# rpi_vga.net
KiCad netlist of a schematic drawn in EAGLE
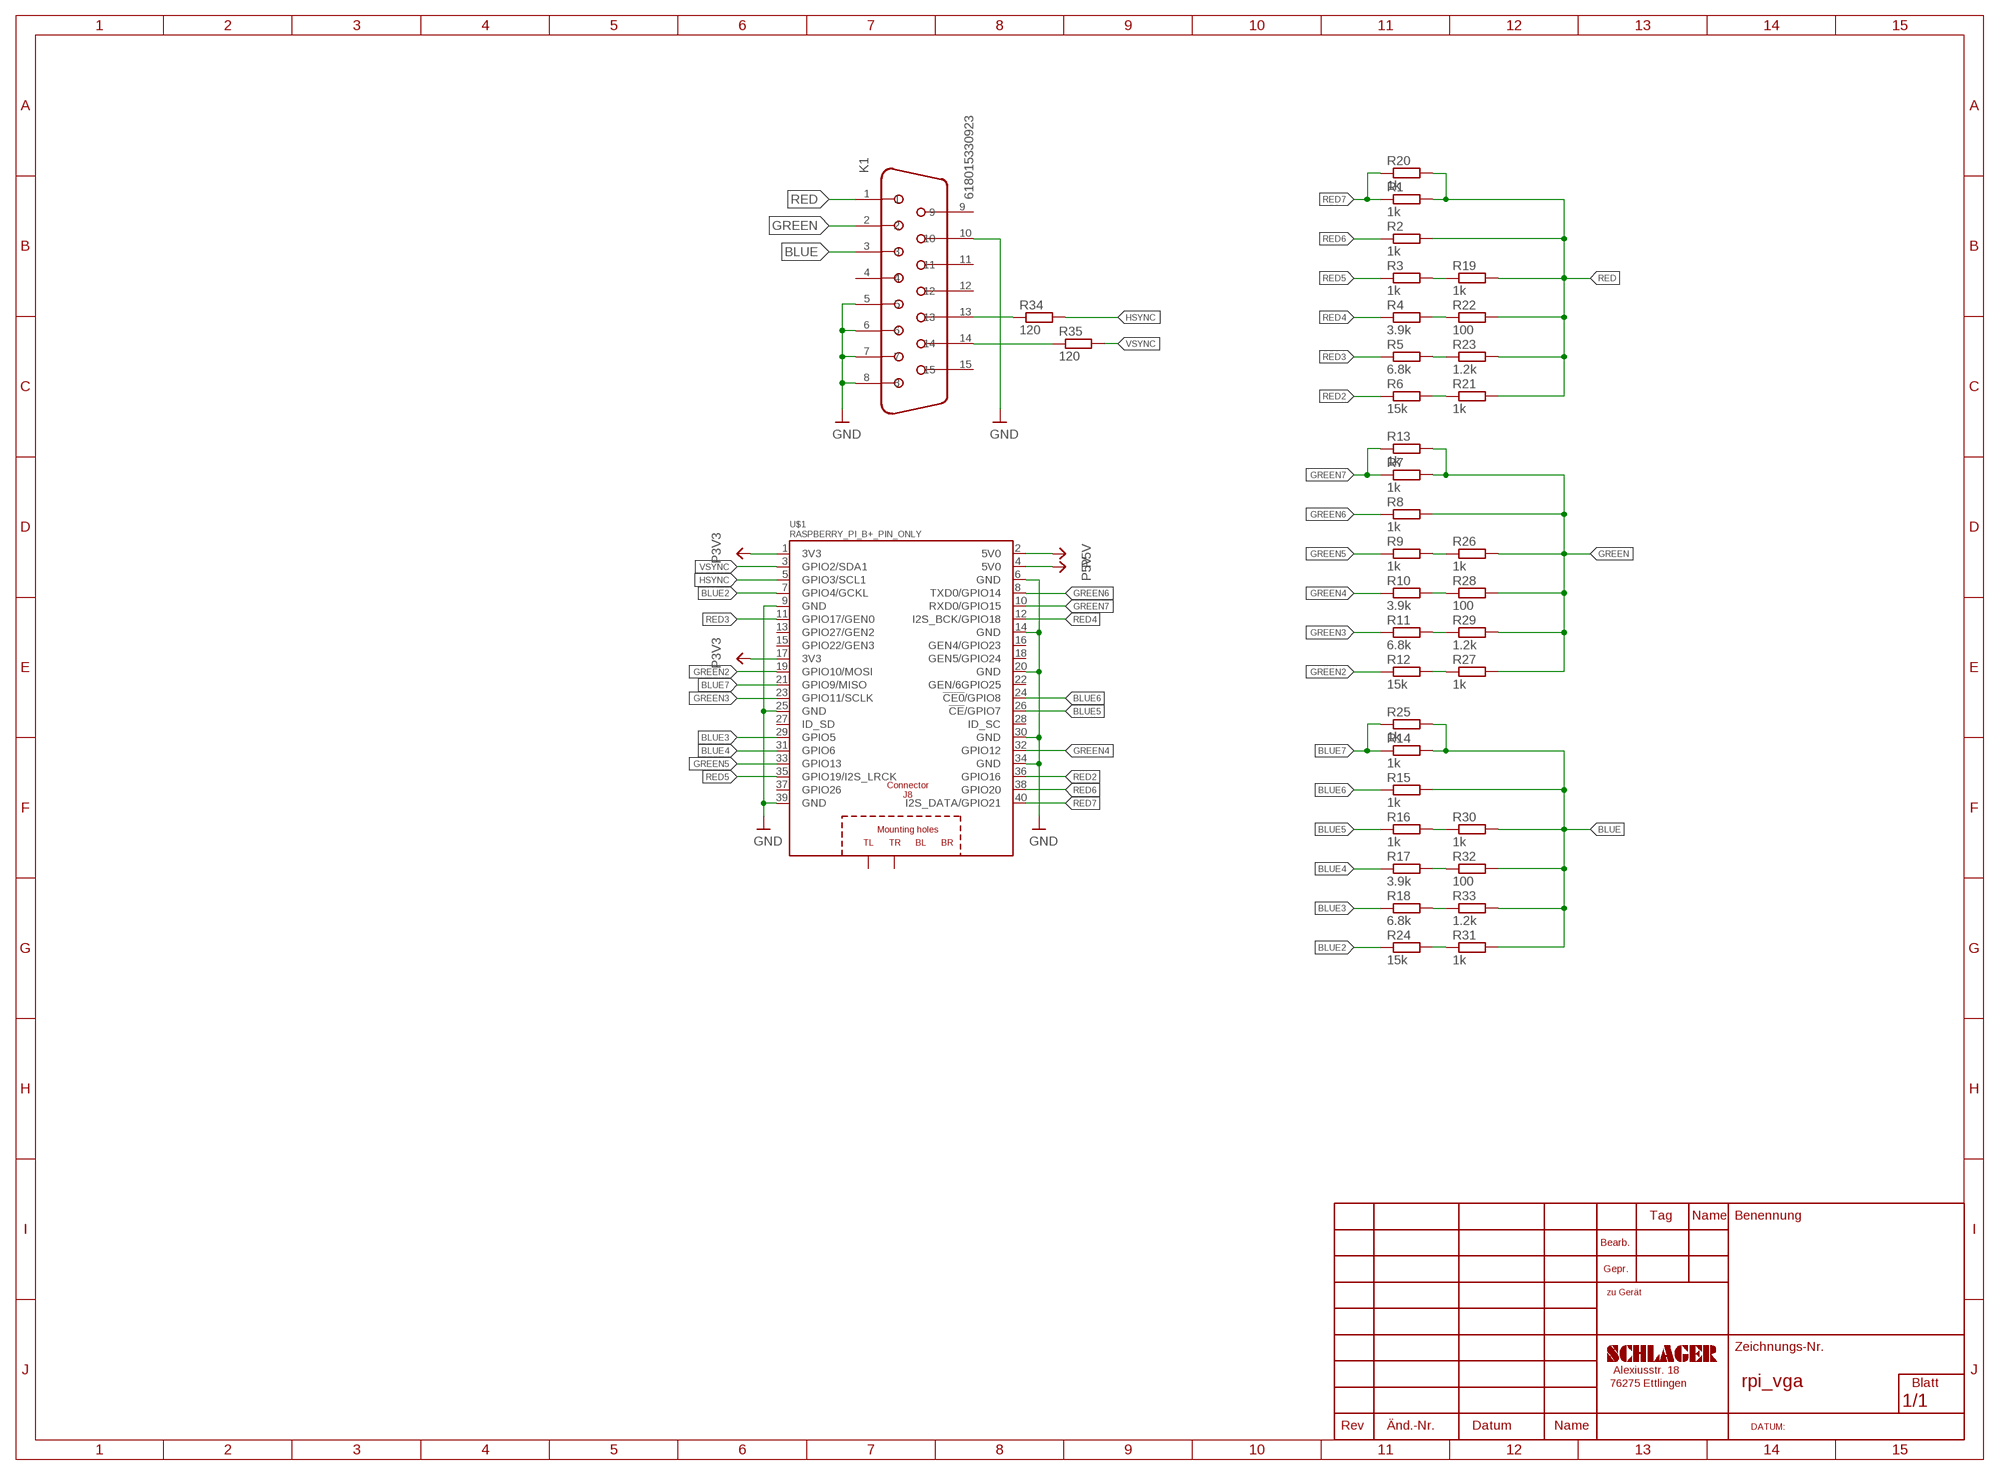
[diagram p0: schematic, sheet 1]

(export (version "E")
  (design (tool "Eeschema 10.0.6"))
  (components
    (comp (ref "K1")
      (value "618015330923")
      (footprint "eagle-import:618015330923")
      (libsource (lib "eagle-import") (part "618015330923"))
    )
    (comp (ref "R1")
      (value "1k")
      (footprint "eagle-import:R0603")
      (libsource (lib "eagle-import") (part "R-EU_R0603"))
    )
    (comp (ref "R2")
      (value "1k")
      (footprint "eagle-import:R0603")
      (libsource (lib "eagle-import") (part "R-EU_R0603"))
    )
    (comp (ref "R3")
      (value "1k")
      (footprint "eagle-import:R0603")
      (libsource (lib "eagle-import") (part "R-EU_R0603"))
    )
    (comp (ref "R4")
      (value "3.9k")
      (footprint "eagle-import:R0603")
      (libsource (lib "eagle-import") (part "R-EU_R0603"))
    )
    (comp (ref "R5")
      (value "6.8k")
      (footprint "eagle-import:R0603")
      (libsource (lib "eagle-import") (part "R-EU_R0603"))
    )
    (comp (ref "R6")
      (value "15k")
      (footprint "eagle-import:R0603")
      (libsource (lib "eagle-import") (part "R-EU_R0603"))
    )
    (comp (ref "R7")
      (value "1k")
      (footprint "eagle-import:R0603")
      (libsource (lib "eagle-import") (part "R-EU_R0603"))
    )
    (comp (ref "R8")
      (value "1k")
      (footprint "eagle-import:R0603")
      (libsource (lib "eagle-import") (part "R-EU_R0603"))
    )
    (comp (ref "R9")
      (value "1k")
      (footprint "eagle-import:R0603")
      (libsource (lib "eagle-import") (part "R-EU_R0603"))
    )
    (comp (ref "R10")
      (value "3.9k")
      (footprint "eagle-import:R0603")
      (libsource (lib "eagle-import") (part "R-EU_R0603"))
    )
    (comp (ref "R11")
      (value "6.8k")
      (footprint "eagle-import:R0603")
      (libsource (lib "eagle-import") (part "R-EU_R0603"))
    )
    (comp (ref "R12")
      (value "15k")
      (footprint "eagle-import:R0603")
      (libsource (lib "eagle-import") (part "R-EU_R0603"))
    )
    (comp (ref "R13")
      (value "1k")
      (footprint "eagle-import:R0603")
      (libsource (lib "eagle-import") (part "R-EU_R0603"))
    )
    (comp (ref "R14")
      (value "1k")
      (footprint "eagle-import:R0603")
      (libsource (lib "eagle-import") (part "R-EU_R0603"))
    )
    (comp (ref "R15")
      (value "1k")
      (footprint "eagle-import:R0603")
      (libsource (lib "eagle-import") (part "R-EU_R0603"))
    )
    (comp (ref "R16")
      (value "1k")
      (footprint "eagle-import:R0603")
      (libsource (lib "eagle-import") (part "R-EU_R0603"))
    )
    (comp (ref "R17")
      (value "3.9k")
      (footprint "eagle-import:R0603")
      (libsource (lib "eagle-import") (part "R-EU_R0603"))
    )
    (comp (ref "R18")
      (value "6.8k")
      (footprint "eagle-import:R0603")
      (libsource (lib "eagle-import") (part "R-EU_R0603"))
    )
    (comp (ref "R19")
      (value "1k")
      (footprint "eagle-import:R0603")
      (libsource (lib "eagle-import") (part "R-EU_R0603"))
    )
    (comp (ref "R20")
      (value "1k")
      (footprint "eagle-import:R0603")
      (libsource (lib "eagle-import") (part "R-EU_R0603"))
    )
    (comp (ref "R21")
      (value "1k")
      (footprint "eagle-import:R0603")
      (libsource (lib "eagle-import") (part "R-EU_R0603"))
    )
    (comp (ref "R22")
      (value "100")
      (footprint "eagle-import:R0603")
      (libsource (lib "eagle-import") (part "R-EU_R0603"))
    )
    (comp (ref "R23")
      (value "1.2k")
      (footprint "eagle-import:R0603")
      (libsource (lib "eagle-import") (part "R-EU_R0603"))
    )
    (comp (ref "R24")
      (value "15k")
      (footprint "eagle-import:R0603")
      (libsource (lib "eagle-import") (part "R-EU_R0603"))
    )
    (comp (ref "R25")
      (value "1k")
      (footprint "eagle-import:R0603")
      (libsource (lib "eagle-import") (part "R-EU_R0603"))
    )
    (comp (ref "R26")
      (value "1k")
      (footprint "eagle-import:R0603")
      (libsource (lib "eagle-import") (part "R-EU_R0603"))
    )
    (comp (ref "R27")
      (value "1k")
      (footprint "eagle-import:R0603")
      (libsource (lib "eagle-import") (part "R-EU_R0603"))
    )
    (comp (ref "R28")
      (value "100")
      (footprint "eagle-import:R0603")
      (libsource (lib "eagle-import") (part "R-EU_R0603"))
    )
    (comp (ref "R29")
      (value "1.2k")
      (footprint "eagle-import:R0603")
      (libsource (lib "eagle-import") (part "R-EU_R0603"))
    )
    (comp (ref "R30")
      (value "1k")
      (footprint "eagle-import:R0603")
      (libsource (lib "eagle-import") (part "R-EU_R0603"))
    )
    (comp (ref "R31")
      (value "1k")
      (footprint "eagle-import:R0603")
      (libsource (lib "eagle-import") (part "R-EU_R0603"))
    )
    (comp (ref "R32")
      (value "100")
      (footprint "eagle-import:R0603")
      (libsource (lib "eagle-import") (part "R-EU_R0603"))
    )
    (comp (ref "R33")
      (value "1.2k")
      (footprint "eagle-import:R0603")
      (libsource (lib "eagle-import") (part "R-EU_R0603"))
    )
    (comp (ref "R34")
      (value "120")
      (footprint "eagle-import:R0603")
      (libsource (lib "eagle-import") (part "R-EU_R0603"))
    )
    (comp (ref "R35")
      (value "120")
      (footprint "eagle-import:R0603")
      (libsource (lib "eagle-import") (part "R-EU_R0603"))
    )
    (comp (ref "U$1")
      (value "RASPBERRY_PI_B+_PIN_ONLY")
      (footprint "eagle-import:RASPBERRY_PI_B+_PIN_ONLY")
      (libsource (lib "eagle-import") (part "RASPBERRY_PI_B+_PIN_ONLY"))
    )
  )
  (nets
    (net (code "1") (name "BLUE") (class "Default")
      (node (ref "K1") (pin "3") (pinfunction "3_3") (pintype "bidirectional"))
      (node (ref "R14") (pin "2") (pinfunction "2_2") (pintype "passive"))
      (node (ref "R15") (pin "2") (pinfunction "2_2") (pintype "passive"))
      (node (ref "R25") (pin "2") (pinfunction "2_2") (pintype "passive"))
      (node (ref "R30") (pin "2") (pinfunction "2_2") (pintype "passive"))
      (node (ref "R31") (pin "2") (pinfunction "2_2") (pintype "passive"))
      (node (ref "R32") (pin "2") (pinfunction "2_2") (pintype "passive"))
      (node (ref "R33") (pin "2") (pinfunction "2_2") (pintype "passive"))
    )
    (net (code "2") (name "BLUE2") (class "Default")
      (node (ref "R24") (pin "1") (pinfunction "1_1") (pintype "passive"))
      (node (ref "U$1") (pin "7") (pinfunction "GPIO4/GCKL_7") (pintype "bidirectional"))
    )
    (net (code "3") (name "BLUE3") (class "Default")
      (node (ref "R18") (pin "1") (pinfunction "1_1") (pintype "passive"))
      (node (ref "U$1") (pin "29") (pinfunction "GPIO5_29") (pintype "bidirectional"))
    )
    (net (code "4") (name "BLUE4") (class "Default")
      (node (ref "R17") (pin "1") (pinfunction "1_1") (pintype "passive"))
      (node (ref "U$1") (pin "31") (pinfunction "GPIO6_31") (pintype "bidirectional"))
    )
    (net (code "5") (name "BLUE5") (class "Default")
      (node (ref "R16") (pin "1") (pinfunction "1_1") (pintype "passive"))
      (node (ref "U$1") (pin "26") (pinfunction "~{CE}/GPIO7_26") (pintype "bidirectional"))
    )
    (net (code "6") (name "BLUE6") (class "Default")
      (node (ref "R15") (pin "1") (pinfunction "1_1") (pintype "passive"))
      (node (ref "U$1") (pin "24") (pinfunction "~{CE0}/GPIO8_24") (pintype "bidirectional"))
    )
    (net (code "7") (name "BLUE7") (class "Default")
      (node (ref "R14") (pin "1") (pinfunction "1_1") (pintype "passive"))
      (node (ref "R25") (pin "1") (pinfunction "1_1") (pintype "passive"))
      (node (ref "U$1") (pin "21") (pinfunction "GPIO9/MISO_21") (pintype "bidirectional"))
    )
    (net (code "8") (name "GND") (class "Default")
      (node (ref "K1") (pin "10") (pinfunction "10_10") (pintype "bidirectional"))
      (node (ref "K1") (pin "5") (pinfunction "5_5") (pintype "bidirectional"))
      (node (ref "K1") (pin "6") (pinfunction "6_6") (pintype "bidirectional"))
      (node (ref "K1") (pin "7") (pinfunction "7_7") (pintype "bidirectional"))
      (node (ref "K1") (pin "8") (pinfunction "8_8") (pintype "bidirectional"))
      (node (ref "U$1") (pin "14") (pinfunction "GND_14") (pintype "power_in"))
      (node (ref "U$1") (pin "20") (pinfunction "GND_20") (pintype "power_in"))
      (node (ref "U$1") (pin "25") (pinfunction "GND_25") (pintype "power_in"))
      (node (ref "U$1") (pin "30") (pinfunction "GND_30") (pintype "power_in"))
      (node (ref "U$1") (pin "34") (pinfunction "GND_34") (pintype "power_in"))
      (node (ref "U$1") (pin "39") (pinfunction "GND_39") (pintype "power_in"))
      (node (ref "U$1") (pin "6") (pinfunction "GND_6") (pintype "power_in"))
      (node (ref "U$1") (pin "9") (pinfunction "GND_9") (pintype "power_in"))
    )
    (net (code "9") (name "GREEN") (class "Default")
      (node (ref "K1") (pin "2") (pinfunction "2_2") (pintype "bidirectional"))
      (node (ref "R13") (pin "2") (pinfunction "2_2") (pintype "passive"))
      (node (ref "R26") (pin "2") (pinfunction "2_2") (pintype "passive"))
      (node (ref "R27") (pin "2") (pinfunction "2_2") (pintype "passive"))
      (node (ref "R28") (pin "2") (pinfunction "2_2") (pintype "passive"))
      (node (ref "R29") (pin "2") (pinfunction "2_2") (pintype "passive"))
      (node (ref "R7") (pin "2") (pinfunction "2_2") (pintype "passive"))
      (node (ref "R8") (pin "2") (pinfunction "2_2") (pintype "passive"))
    )
    (net (code "10") (name "GREEN2") (class "Default")
      (node (ref "R12") (pin "1") (pinfunction "1_1") (pintype "passive"))
      (node (ref "U$1") (pin "19") (pinfunction "GPIO10/MOSI_19") (pintype "bidirectional"))
    )
    (net (code "11") (name "GREEN3") (class "Default")
      (node (ref "R11") (pin "1") (pinfunction "1_1") (pintype "passive"))
      (node (ref "U$1") (pin "23") (pinfunction "GPIO11/SCLK_23") (pintype "bidirectional"))
    )
    (net (code "12") (name "GREEN4") (class "Default")
      (node (ref "R10") (pin "1") (pinfunction "1_1") (pintype "passive"))
      (node (ref "U$1") (pin "32") (pinfunction "GPIO12_32") (pintype "bidirectional"))
    )
    (net (code "13") (name "GREEN5") (class "Default")
      (node (ref "R9") (pin "1") (pinfunction "1_1") (pintype "passive"))
      (node (ref "U$1") (pin "33") (pinfunction "GPIO13_33") (pintype "bidirectional"))
    )
    (net (code "14") (name "GREEN6") (class "Default")
      (node (ref "R8") (pin "1") (pinfunction "1_1") (pintype "passive"))
      (node (ref "U$1") (pin "8") (pinfunction "TXD0/GPIO14_8") (pintype "bidirectional"))
    )
    (net (code "15") (name "GREEN7") (class "Default")
      (node (ref "R13") (pin "1") (pinfunction "1_1") (pintype "passive"))
      (node (ref "R7") (pin "1") (pinfunction "1_1") (pintype "passive"))
      (node (ref "U$1") (pin "10") (pinfunction "RXD0/GPIO15_10") (pintype "bidirectional"))
    )
    (net (code "16") (name "HSYNC") (class "Default")
      (node (ref "R34") (pin "2") (pinfunction "2_2") (pintype "passive"))
      (node (ref "U$1") (pin "5") (pinfunction "GPIO3/SCL1_5") (pintype "bidirectional"))
    )
    (net (code "17") (name "Net-(K1-Pad13)") (class "Default")
      (node (ref "K1") (pin "13") (pinfunction "13_13") (pintype "bidirectional"))
      (node (ref "R34") (pin "1") (pinfunction "1_1") (pintype "passive"))
    )
    (net (code "18") (name "Net-(K1-Pad14)") (class "Default")
      (node (ref "K1") (pin "14") (pinfunction "14_14") (pintype "bidirectional"))
      (node (ref "R35") (pin "1") (pinfunction "1_1") (pintype "passive"))
    )
    (net (code "19") (name "Net-(R10-Pad2)") (class "Default")
      (node (ref "R10") (pin "2") (pinfunction "2_2") (pintype "passive"))
      (node (ref "R28") (pin "1") (pinfunction "1_1") (pintype "passive"))
    )
    (net (code "20") (name "Net-(R11-Pad2)") (class "Default")
      (node (ref "R11") (pin "2") (pinfunction "2_2") (pintype "passive"))
      (node (ref "R29") (pin "1") (pinfunction "1_1") (pintype "passive"))
    )
    (net (code "21") (name "Net-(R12-Pad2)") (class "Default")
      (node (ref "R12") (pin "2") (pinfunction "2_2") (pintype "passive"))
      (node (ref "R27") (pin "1") (pinfunction "1_1") (pintype "passive"))
    )
    (net (code "22") (name "Net-(R16-Pad2)") (class "Default")
      (node (ref "R16") (pin "2") (pinfunction "2_2") (pintype "passive"))
      (node (ref "R30") (pin "1") (pinfunction "1_1") (pintype "passive"))
    )
    (net (code "23") (name "Net-(R17-Pad2)") (class "Default")
      (node (ref "R17") (pin "2") (pinfunction "2_2") (pintype "passive"))
      (node (ref "R32") (pin "1") (pinfunction "1_1") (pintype "passive"))
    )
    (net (code "24") (name "Net-(R18-Pad2)") (class "Default")
      (node (ref "R18") (pin "2") (pinfunction "2_2") (pintype "passive"))
      (node (ref "R33") (pin "1") (pinfunction "1_1") (pintype "passive"))
    )
    (net (code "25") (name "Net-(R19-Pad1)") (class "Default")
      (node (ref "R19") (pin "1") (pinfunction "1_1") (pintype "passive"))
      (node (ref "R3") (pin "2") (pinfunction "2_2") (pintype "passive"))
    )
    (net (code "26") (name "Net-(R21-Pad1)") (class "Default")
      (node (ref "R21") (pin "1") (pinfunction "1_1") (pintype "passive"))
      (node (ref "R6") (pin "2") (pinfunction "2_2") (pintype "passive"))
    )
    (net (code "27") (name "Net-(R22-Pad1)") (class "Default")
      (node (ref "R22") (pin "1") (pinfunction "1_1") (pintype "passive"))
      (node (ref "R4") (pin "2") (pinfunction "2_2") (pintype "passive"))
    )
    (net (code "28") (name "Net-(R23-Pad1)") (class "Default")
      (node (ref "R23") (pin "1") (pinfunction "1_1") (pintype "passive"))
      (node (ref "R5") (pin "2") (pinfunction "2_2") (pintype "passive"))
    )
    (net (code "29") (name "Net-(R24-Pad2)") (class "Default")
      (node (ref "R24") (pin "2") (pinfunction "2_2") (pintype "passive"))
      (node (ref "R31") (pin "1") (pinfunction "1_1") (pintype "passive"))
    )
    (net (code "30") (name "Net-(R26-Pad1)") (class "Default")
      (node (ref "R26") (pin "1") (pinfunction "1_1") (pintype "passive"))
      (node (ref "R9") (pin "2") (pinfunction "2_2") (pintype "passive"))
    )
    (net (code "31") (name "P3V3") (class "Default")
      (node (ref "U$1") (pin "1") (pinfunction "3V3_1") (pintype "power_in"))
      (node (ref "U$1") (pin "17") (pinfunction "3V3_17") (pintype "power_in"))
    )
    (net (code "32") (name "P5V") (class "Default")
      (node (ref "U$1") (pin "2") (pinfunction "5V0_2") (pintype "power_in"))
      (node (ref "U$1") (pin "4") (pinfunction "5V0_4") (pintype "power_in"))
    )
    (net (code "33") (name "RED") (class "Default")
      (node (ref "K1") (pin "1") (pinfunction "1_1") (pintype "bidirectional"))
      (node (ref "R1") (pin "2") (pinfunction "2_2") (pintype "passive"))
      (node (ref "R19") (pin "2") (pinfunction "2_2") (pintype "passive"))
      (node (ref "R2") (pin "2") (pinfunction "2_2") (pintype "passive"))
      (node (ref "R20") (pin "2") (pinfunction "2_2") (pintype "passive"))
      (node (ref "R21") (pin "2") (pinfunction "2_2") (pintype "passive"))
      (node (ref "R22") (pin "2") (pinfunction "2_2") (pintype "passive"))
      (node (ref "R23") (pin "2") (pinfunction "2_2") (pintype "passive"))
    )
    (net (code "34") (name "RED2") (class "Default")
      (node (ref "R6") (pin "1") (pinfunction "1_1") (pintype "passive"))
      (node (ref "U$1") (pin "36") (pinfunction "GPIO16_36") (pintype "bidirectional"))
    )
    (net (code "35") (name "RED3") (class "Default")
      (node (ref "R5") (pin "1") (pinfunction "1_1") (pintype "passive"))
      (node (ref "U$1") (pin "11") (pinfunction "GPIO17/GEN0_11") (pintype "bidirectional"))
    )
    (net (code "36") (name "RED4") (class "Default")
      (node (ref "R4") (pin "1") (pinfunction "1_1") (pintype "passive"))
      (node (ref "U$1") (pin "12") (pinfunction "I2S_BCK/GPIO18_12") (pintype "bidirectional"))
    )
    (net (code "37") (name "RED5") (class "Default")
      (node (ref "R3") (pin "1") (pinfunction "1_1") (pintype "passive"))
      (node (ref "U$1") (pin "35") (pinfunction "GPIO19/I2S_LRCK_35") (pintype "bidirectional"))
    )
    (net (code "38") (name "RED6") (class "Default")
      (node (ref "R2") (pin "1") (pinfunction "1_1") (pintype "passive"))
      (node (ref "U$1") (pin "38") (pinfunction "GPIO20_38") (pintype "bidirectional"))
    )
    (net (code "39") (name "RED7") (class "Default")
      (node (ref "R1") (pin "1") (pinfunction "1_1") (pintype "passive"))
      (node (ref "R20") (pin "1") (pinfunction "1_1") (pintype "passive"))
      (node (ref "U$1") (pin "40") (pinfunction "I2S_DATA/GPIO21_40") (pintype "bidirectional"))
    )
    (net (code "40") (name "VSYNC") (class "Default")
      (node (ref "R35") (pin "2") (pinfunction "2_2") (pintype "passive"))
      (node (ref "U$1") (pin "3") (pinfunction "GPIO2/SDA1_3") (pintype "bidirectional"))
    )
    (net (code "41") (name "unconnected-(K1-Pad4)") (class "Default")
      (node (ref "K1") (pin "4") (pinfunction "4_4") (pintype "bidirectional"))
    )
    (net (code "42") (name "unconnected-(K1-Pad9)") (class "Default")
      (node (ref "K1") (pin "9") (pinfunction "9_9") (pintype "bidirectional"))
    )
    (net (code "43") (name "unconnected-(K1-Pad11)") (class "Default")
      (node (ref "K1") (pin "11") (pinfunction "11_11") (pintype "bidirectional"))
    )
    (net (code "44") (name "unconnected-(K1-Pad12)") (class "Default")
      (node (ref "K1") (pin "12") (pinfunction "12_12") (pintype "bidirectional"))
    )
    (net (code "45") (name "unconnected-(K1-Pad15)") (class "Default")
      (node (ref "K1") (pin "15") (pinfunction "15_15") (pintype "bidirectional"))
    )
    (net (code "46") (name "unconnected-(U$1-GEN4{slash}GPIO23-Pad16)") (class "Default")
      (node (ref "U$1") (pin "16") (pinfunction "GEN4/GPIO23_16") (pintype "bidirectional"))
    )
    (net (code "47") (name "unconnected-(U$1-GEN5{slash}GPIO24-Pad18)") (class "Default")
      (node (ref "U$1") (pin "18") (pinfunction "GEN5/GPIO24_18") (pintype "bidirectional"))
    )
    (net (code "48") (name "unconnected-(U$1-GEN{slash}6GPIO25-Pad22)") (class "Default")
      (node (ref "U$1") (pin "22") (pinfunction "GEN/6GPIO25_22") (pintype "bidirectional"))
    )
    (net (code "49") (name "unconnected-(U$1-GPIO22{slash}GEN3-Pad15)") (class "Default")
      (node (ref "U$1") (pin "15") (pinfunction "GPIO22/GEN3_15") (pintype "bidirectional"))
    )
    (net (code "50") (name "unconnected-(U$1-GPIO26-Pad37)") (class "Default")
      (node (ref "U$1") (pin "37") (pinfunction "GPIO26_37") (pintype "bidirectional"))
    )
    (net (code "51") (name "unconnected-(U$1-GPIO27{slash}GEN2-Pad13)") (class "Default")
      (node (ref "U$1") (pin "13") (pinfunction "GPIO27/GEN2_13") (pintype "bidirectional"))
    )
    (net (code "52") (name "unconnected-(U$1-ID_SC-Pad28)") (class "Default")
      (node (ref "U$1") (pin "28") (pinfunction "ID_SC_28") (pintype "bidirectional"))
    )
    (net (code "53") (name "unconnected-(U$1-ID_SD-Pad27)") (class "Default")
      (node (ref "U$1") (pin "27") (pinfunction "ID_SD_27") (pintype "bidirectional"))
    )
    (net (code "54") (name "unconnected-(U$1-TL-PadPE_TL)") (class "Default")
      (node (ref "U$1") (pin "PE_TL") (pinfunction "TL_PE_TL") (pintype "bidirectional"))
    )
    (net (code "55") (name "unconnected-(U$1-TR-PadPE_TR)") (class "Default")
      (node (ref "U$1") (pin "PE_TR") (pinfunction "TR_PE_TR") (pintype "bidirectional"))
    )
  )
)
